# JTAG_Trace.net
KiCad netlist of a schematic drawn in Altium Designer
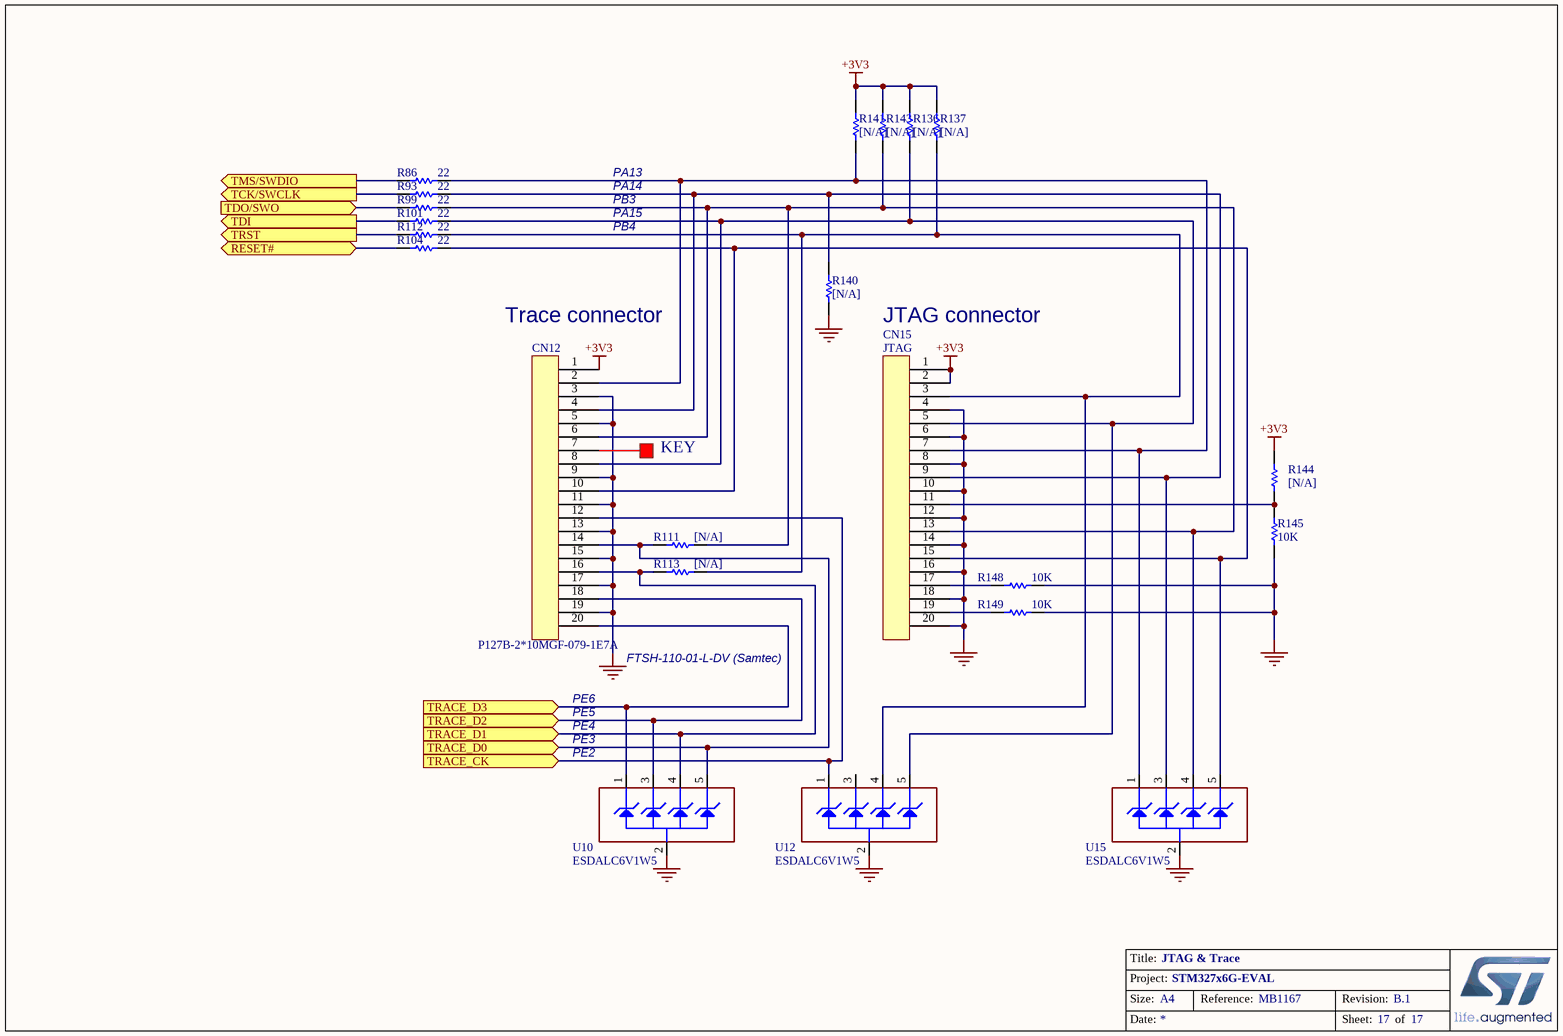
[diagram p0: JTAG&Trace.SchDoc]

(export (version "E")
  (design (tool "Eeschema 10.0.6"))
  (components
    (comp (ref "CN12")
      (value "P127B-2*10MGF-079-1E7A")
      (footprint "FTSH-110-01-L-DV")
      (libsource (lib "*") (part "20PIN1"))
    )
    (comp (ref "CN15") (value "JTAG") (footprint "IDC20S") (libsource (lib "*") (part "20PIN1")))
    (comp (ref "R86")
      (value "22")
      (footprint "0603R")
      (description "Resistor")
      (fields (field (name "PUBLISHER") "Altium Limited"))
      (libsource (lib "Miscellaneous Devices") (part "Res1"))
    )
    (comp (ref "R93")
      (value "22")
      (footprint "0603R")
      (description "Resistor")
      (fields (field (name "PUBLISHER") "Altium Limited"))
      (libsource (lib "Miscellaneous Devices") (part "Res1"))
    )
    (comp (ref "R99")
      (value "22")
      (footprint "0603R")
      (description "Resistor")
      (fields (field (name "PUBLISHER") "Altium Limited"))
      (libsource (lib "Miscellaneous Devices") (part "Res1"))
    )
    (comp (ref "R101")
      (value "22")
      (footprint "0603R")
      (description "Resistor")
      (fields (field (name "PUBLISHER") "Altium Limited"))
      (libsource (lib "Miscellaneous Devices") (part "Res1"))
    )
    (comp (ref "R104")
      (value "22")
      (footprint "0603R")
      (description "Resistor")
      (fields (field (name "PUBLISHER") "Altium Limited"))
      (libsource (lib "Miscellaneous Devices") (part "Res1"))
    )
    (comp (ref "R111")
      (value "[N/A]")
      (footprint "0603R")
      (description "Resistor")
      (fields (field (name "PUBLISHER") "Altium Limited"))
      (libsource (lib "Miscellaneous Devices") (part "Res1"))
    )
    (comp (ref "R112")
      (value "22")
      (footprint "0603R")
      (description "Resistor")
      (fields (field (name "PUBLISHER") "Altium Limited"))
      (libsource (lib "Miscellaneous Devices") (part "Res1"))
    )
    (comp (ref "R113")
      (value "[N/A]")
      (footprint "0603R")
      (description "Resistor")
      (fields (field (name "PUBLISHER") "Altium Limited"))
      (libsource (lib "Miscellaneous Devices") (part "Res1"))
    )
    (comp (ref "R136")
      (value "[N/A]")
      (footprint "0603R")
      (description "Resistor")
      (fields (field (name "PUBLISHER") "Altium Limited"))
      (libsource (lib "Miscellaneous Devices") (part "Res1"))
    )
    (comp (ref "R137")
      (value "[N/A]")
      (footprint "0603R")
      (description "Resistor")
      (fields (field (name "PUBLISHER") "Altium Limited"))
      (libsource (lib "Miscellaneous Devices") (part "Res1"))
    )
    (comp (ref "R140")
      (value "[N/A]")
      (footprint "0603R")
      (description "Resistor")
      (fields (field (name "PUBLISHER") "Altium Limited"))
      (libsource (lib "Miscellaneous Devices") (part "Res1"))
    )
    (comp (ref "R141")
      (value "[N/A]")
      (footprint "0603R")
      (description "Resistor")
      (fields (field (name "PUBLISHER") "Altium Limited"))
      (libsource (lib "Miscellaneous Devices") (part "Res1"))
    )
    (comp (ref "R143")
      (value "[N/A]")
      (footprint "0603R")
      (description "Resistor")
      (fields (field (name "PUBLISHER") "Altium Limited"))
      (libsource (lib "Miscellaneous Devices") (part "Res1"))
    )
    (comp (ref "R144")
      (value "[N/A]")
      (footprint "0603R")
      (description "Resistor")
      (fields (field (name "PUBLISHER") "Altium Limited"))
      (libsource (lib "Miscellaneous Devices") (part "Res1"))
    )
    (comp (ref "R145")
      (value "10K")
      (footprint "0603R")
      (description "Resistor")
      (fields (field (name "PUBLISHER") "Altium Limited"))
      (libsource (lib "Miscellaneous Devices") (part "Res1"))
    )
    (comp (ref "R148")
      (value "10K")
      (footprint "0603R")
      (description "Resistor")
      (fields (field (name "PUBLISHER") "Altium Limited"))
      (libsource (lib "Miscellaneous Devices") (part "Res1"))
    )
    (comp (ref "R149")
      (value "10K")
      (footprint "0603R")
      (description "Resistor")
      (fields (field (name "PUBLISHER") "Altium Limited"))
      (libsource (lib "Miscellaneous Devices") (part "Res1"))
    )
    (comp (ref "U10")
      (value "ESDALC6V1W5")
      (footprint "SOT-353")
      (description "Dual Transil array for ESD protection")
      (libsource (lib "MB1167_1") (part "ESDALC6V1W5"))
    )
    (comp (ref "U12")
      (value "ESDALC6V1W5")
      (footprint "SOT-353")
      (description "Dual Transil array for ESD protection")
      (libsource (lib "MB1167_1") (part "ESDALC6V1W5"))
    )
    (comp (ref "U15")
      (value "ESDALC6V1W5")
      (footprint "SOT-353")
      (description "Dual Transil array for ESD protection")
      (libsource (lib "MB1167_1") (part "ESDALC6V1W5"))
    )
  )
  (nets
    (net (code "1") (name "+3V3") (class "Default")
      (node (ref "CN12") (pin "1") (pintype "passive"))
      (node (ref "CN15") (pin "1") (pintype "passive"))
      (node (ref "CN15") (pin "2") (pintype "passive"))
      (node (ref "R136") (pin "2") (pinfunction "2_2") (pintype "passive"))
      (node (ref "R137") (pin "2") (pinfunction "2_2") (pintype "passive"))
      (node (ref "R141") (pin "2") (pinfunction "2_2") (pintype "passive"))
      (node (ref "R143") (pin "2") (pinfunction "2_2") (pintype "passive"))
      (node (ref "R144") (pin "2") (pinfunction "2_2") (pintype "passive"))
    )
    (net (code "2") (name "/RESET#") (class "Default")
      (node (ref "R104") (pin "2") (pinfunction "2_2") (pintype "passive"))
    )
    (net (code "3") (name "/TCK{slash}SWCLK") (class "Default")
      (node (ref "R93") (pin "2") (pinfunction "2_2") (pintype "passive"))
    )
    (net (code "4") (name "/TDI") (class "Default")
      (node (ref "R101") (pin "2") (pinfunction "2_2") (pintype "passive"))
    )
    (net (code "5") (name "/TDO{slash}SWO") (class "Default")
      (node (ref "R99") (pin "2") (pinfunction "2_2") (pintype "passive"))
    )
    (net (code "6") (name "/TMS{slash}SWDIO") (class "Default")
      (node (ref "R86") (pin "2") (pinfunction "2_2") (pintype "passive"))
    )
    (net (code "7") (name "/TRACE_CK") (class "Default")
      (node (ref "CN12") (pin "12") (pintype "passive"))
      (node (ref "U12") (pin "1") (pinfunction "IO1_1") (pintype "passive"))
    )
    (net (code "8") (name "/TRACE_D0") (class "Default")
      (node (ref "CN12") (pin "14") (pintype "passive"))
      (node (ref "R111") (pin "1") (pinfunction "1_1") (pintype "passive"))
      (node (ref "U10") (pin "5") (pinfunction "IO4_5") (pintype "passive"))
    )
    (net (code "9") (name "/TRACE_D1") (class "Default")
      (node (ref "CN12") (pin "16") (pintype "passive"))
      (node (ref "R113") (pin "1") (pinfunction "1_1") (pintype "passive"))
      (node (ref "U10") (pin "4") (pinfunction "IO3_4") (pintype "passive"))
    )
    (net (code "10") (name "/TRACE_D2") (class "Default")
      (node (ref "CN12") (pin "18") (pintype "passive"))
      (node (ref "U10") (pin "3") (pinfunction "IO2_3") (pintype "passive"))
    )
    (net (code "11") (name "/TRACE_D3") (class "Default")
      (node (ref "CN12") (pin "20") (pintype "passive"))
      (node (ref "U10") (pin "1") (pinfunction "IO1_1") (pintype "passive"))
    )
    (net (code "12") (name "/TRST") (class "Default")
      (node (ref "R112") (pin "2") (pinfunction "2_2") (pintype "passive"))
    )
    (net (code "13") (name "GND") (class "Default")
      (node (ref "CN12") (pin "11") (pintype "passive"))
      (node (ref "CN12") (pin "13") (pintype "passive"))
      (node (ref "CN12") (pin "15") (pintype "passive"))
      (node (ref "CN12") (pin "17") (pintype "passive"))
      (node (ref "CN12") (pin "19") (pintype "passive"))
      (node (ref "CN12") (pin "3") (pintype "passive"))
      (node (ref "CN12") (pin "5") (pintype "passive"))
      (node (ref "CN12") (pin "9") (pintype "passive"))
      (node (ref "CN15") (pin "10") (pintype "passive"))
      (node (ref "CN15") (pin "12") (pintype "passive"))
      (node (ref "CN15") (pin "14") (pintype "passive"))
      (node (ref "CN15") (pin "16") (pintype "passive"))
      (node (ref "CN15") (pin "18") (pintype "passive"))
      (node (ref "CN15") (pin "20") (pintype "passive"))
      (node (ref "CN15") (pin "4") (pintype "passive"))
      (node (ref "CN15") (pin "6") (pintype "passive"))
      (node (ref "CN15") (pin "8") (pintype "passive"))
      (node (ref "R140") (pin "1") (pinfunction "1_1") (pintype "passive"))
      (node (ref "R145") (pin "1") (pinfunction "1_1") (pintype "passive"))
      (node (ref "R148") (pin "1") (pinfunction "1_1") (pintype "passive"))
      (node (ref "R149") (pin "1") (pinfunction "1_1") (pintype "passive"))
      (node (ref "U10") (pin "2") (pinfunction "GND_2") (pintype "passive"))
      (node (ref "U12") (pin "2") (pinfunction "GND_2") (pintype "passive"))
      (node (ref "U15") (pin "2") (pinfunction "GND_2") (pintype "passive"))
    )
    (net (code "14") (name "Net-(CN15-Pad11)") (class "Default")
      (node (ref "CN15") (pin "11") (pintype "passive"))
      (node (ref "R144") (pin "1") (pinfunction "1_1") (pintype "passive"))
      (node (ref "R145") (pin "2") (pinfunction "2_2") (pintype "passive"))
    )
    (net (code "15") (name "Net-(CN15-Pad17)") (class "Default")
      (node (ref "CN15") (pin "17") (pintype "passive"))
      (node (ref "R148") (pin "2") (pinfunction "2_2") (pintype "passive"))
    )
    (net (code "16") (name "Net-(CN15-Pad19)") (class "Default")
      (node (ref "CN15") (pin "19") (pintype "passive"))
      (node (ref "R149") (pin "2") (pinfunction "2_2") (pintype "passive"))
    )
    (net (code "17") (name "Net-(U12-IO3)") (class "Default")
      (node (ref "CN15") (pin "3") (pintype "passive"))
      (node (ref "R112") (pin "1") (pinfunction "1_1") (pintype "passive"))
      (node (ref "R113") (pin "2") (pinfunction "2_2") (pintype "passive"))
      (node (ref "R137") (pin "1") (pinfunction "1_1") (pintype "passive"))
      (node (ref "U12") (pin "4") (pinfunction "IO3_4") (pintype "passive"))
    )
    (net (code "18") (name "Net-(U12-IO4)") (class "Default")
      (node (ref "CN12") (pin "8") (pintype "passive"))
      (node (ref "CN15") (pin "5") (pintype "passive"))
      (node (ref "R101") (pin "1") (pinfunction "1_1") (pintype "passive"))
      (node (ref "R136") (pin "1") (pinfunction "1_1") (pintype "passive"))
      (node (ref "U12") (pin "5") (pinfunction "IO4_5") (pintype "passive"))
    )
    (net (code "19") (name "Net-(U15-IO1)") (class "Default")
      (node (ref "CN12") (pin "2") (pintype "passive"))
      (node (ref "CN15") (pin "7") (pintype "passive"))
      (node (ref "R141") (pin "1") (pinfunction "1_1") (pintype "passive"))
      (node (ref "R86") (pin "1") (pinfunction "1_1") (pintype "passive"))
      (node (ref "U15") (pin "1") (pinfunction "IO1_1") (pintype "passive"))
    )
    (net (code "20") (name "Net-(U15-IO2)") (class "Default")
      (node (ref "CN12") (pin "4") (pintype "passive"))
      (node (ref "CN15") (pin "9") (pintype "passive"))
      (node (ref "R140") (pin "2") (pinfunction "2_2") (pintype "passive"))
      (node (ref "R93") (pin "1") (pinfunction "1_1") (pintype "passive"))
      (node (ref "U15") (pin "3") (pinfunction "IO2_3") (pintype "passive"))
    )
    (net (code "21") (name "Net-(U15-IO3)") (class "Default")
      (node (ref "CN12") (pin "6") (pintype "passive"))
      (node (ref "CN15") (pin "13") (pintype "passive"))
      (node (ref "R111") (pin "2") (pinfunction "2_2") (pintype "passive"))
      (node (ref "R143") (pin "1") (pinfunction "1_1") (pintype "passive"))
      (node (ref "R99") (pin "1") (pinfunction "1_1") (pintype "passive"))
      (node (ref "U15") (pin "4") (pinfunction "IO3_4") (pintype "passive"))
    )
    (net (code "22") (name "Net-(U15-IO4)") (class "Default")
      (node (ref "CN12") (pin "10") (pintype "passive"))
      (node (ref "CN15") (pin "15") (pintype "passive"))
      (node (ref "R104") (pin "1") (pinfunction "1_1") (pintype "passive"))
      (node (ref "U15") (pin "5") (pinfunction "IO4_5") (pintype "passive"))
    )
    (net (code "23") (name "unconnected-(CN12-Pad7)") (class "Default")
      (node (ref "CN12") (pin "7") (pintype "passive"))
    )
    (net (code "24") (name "unconnected-(U12-IO2-Pad3)") (class "Default")
      (node (ref "U12") (pin "3") (pinfunction "IO2_3") (pintype "passive"))
    )
  )
)
